# V7_2024-09-14.net
KiCad netlist of a schematic drawn in EasyEDA Pro
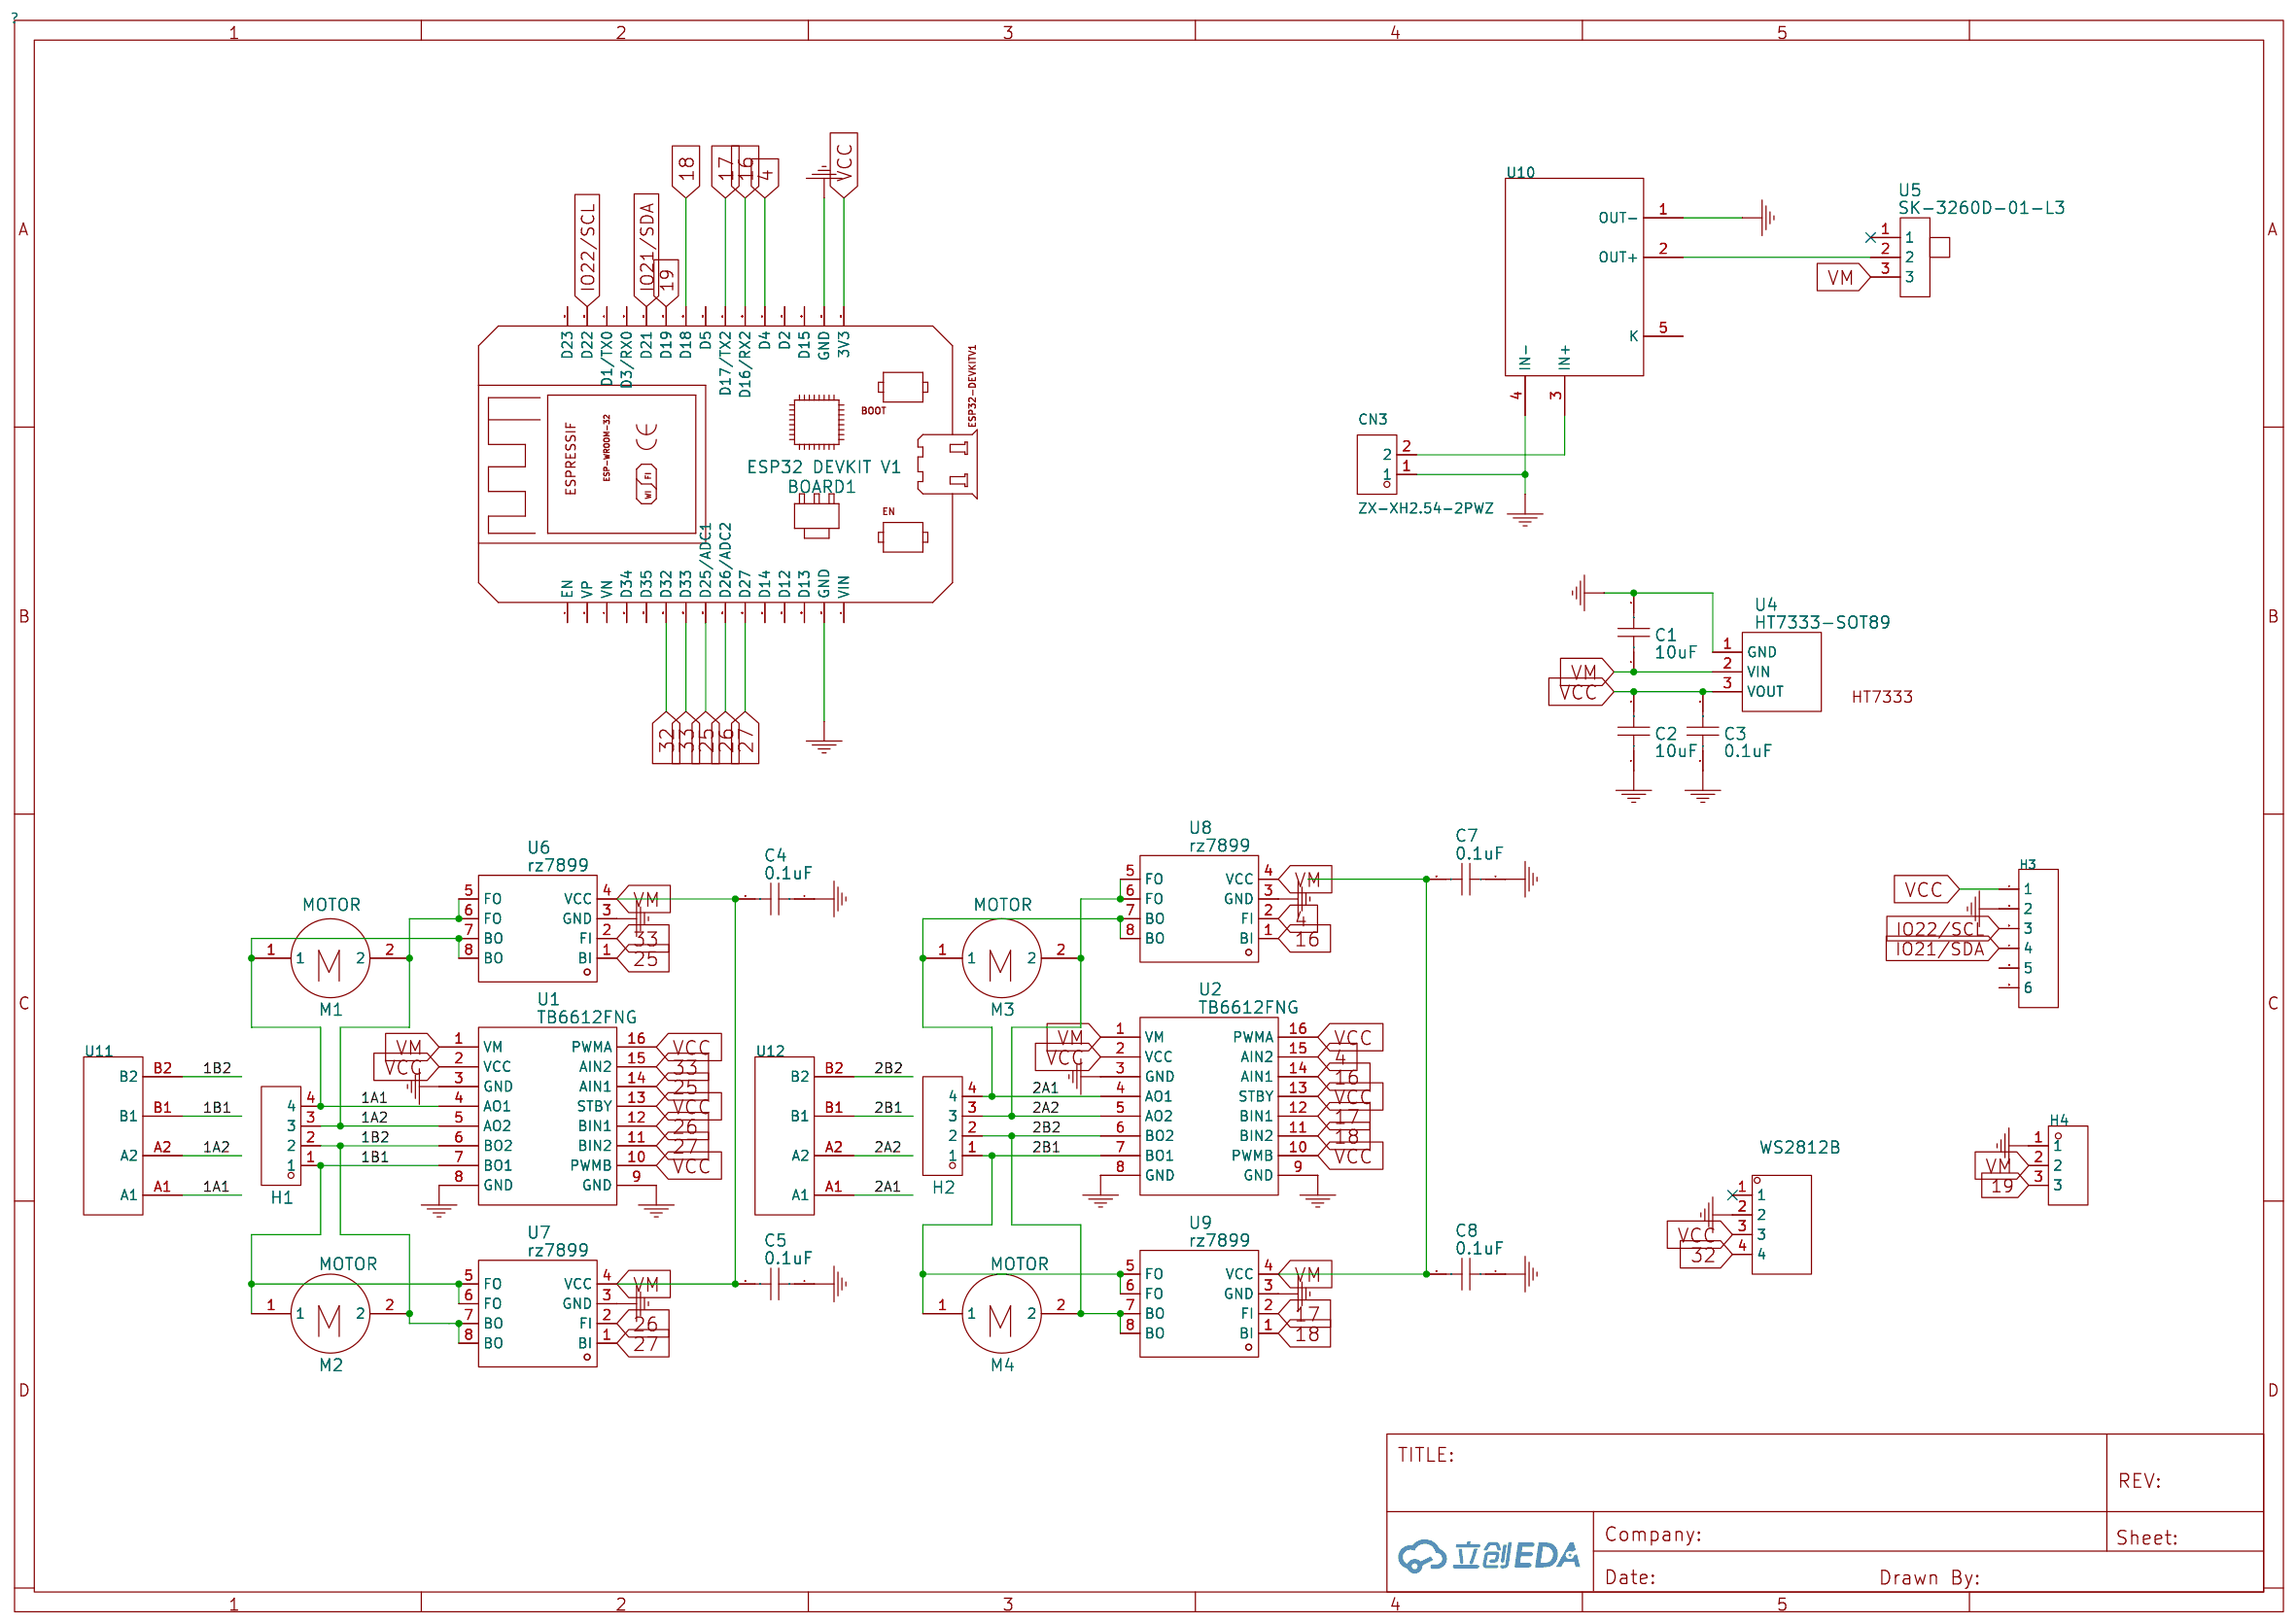
[diagram p0: schematic sheet]

(export (version "E")
  (design (tool "Eeschema 10.0.6"))
  (components
    (comp (ref "BOARD1")
      (value "ESP32 DEVKIT V1")
      (footprint "easyedapro:ESP32-DEVKITV1")
      (libsource (lib "easyedapro") (part "ESP32 DEVKIT V1"))
    )
    (comp (ref "C1")
      (value "10uF")
      (footprint "easyedapro:C0805")
      (fields
        (field (name "Manufacturer Part") "0603F225M250NT")
        (field (name "Manufacturer") "Guangdong Fenghua Advanced Tech")
      )
      (libsource (lib "easyedapro") (part "10uF"))
    )
    (comp (ref "C2")
      (value "10uF")
      (footprint "easyedapro:C0805")
      (fields
        (field (name "Manufacturer Part") "0603F225M250NT")
        (field (name "Manufacturer") "Guangdong Fenghua Advanced Tech")
      )
      (libsource (lib "easyedapro") (part "10uF"))
    )
    (comp (ref "C3")
      (value "0.1uF")
      (footprint "easyedapro:C0805")
      (fields
        (field (name "Manufacturer Part") "0603F225M250NT")
        (field (name "Manufacturer") "Guangdong Fenghua Advanced Tech")
      )
      (libsource (lib "easyedapro") (part "10uF"))
    )
    (comp (ref "C4")
      (value "0.1uF")
      (footprint "easyedapro:C0805")
      (fields
        (field (name "Manufacturer Part") "0603F225M250NT")
        (field (name "Manufacturer") "Guangdong Fenghua Advanced Tech")
      )
      (libsource (lib "easyedapro") (part "10uF"))
    )
    (comp (ref "C5")
      (value "0.1uF")
      (footprint "easyedapro:C0805")
      (fields
        (field (name "Manufacturer Part") "0603F225M250NT")
        (field (name "Manufacturer") "Guangdong Fenghua Advanced Tech")
      )
      (libsource (lib "easyedapro") (part "10uF"))
    )
    (comp (ref "C7")
      (value "0.1uF")
      (footprint "easyedapro:C0805")
      (fields
        (field (name "Manufacturer Part") "0603F225M250NT")
        (field (name "Manufacturer") "Guangdong Fenghua Advanced Tech")
      )
      (libsource (lib "easyedapro") (part "10uF"))
    )
    (comp (ref "C8")
      (value "0.1uF")
      (footprint "easyedapro:C0805")
      (fields
        (field (name "Manufacturer Part") "0603F225M250NT")
        (field (name "Manufacturer") "Guangdong Fenghua Advanced Tech")
      )
      (libsource (lib "easyedapro") (part "10uF"))
    )
    (comp (ref "CN3")
      (value "ZX-XH2.54-2PWZ")
      (footprint "easyedapro:CONN-TH_2P-P2.50_ZX-XH2.54-2PWZ")
      (fields (field (name "Manufacturer") "Megastar(兆星)"))
      (libsource (lib "easyedapro") (part "ZX-XH2.54-2PWZ"))
    )
    (comp (ref "H1")
      (value "GP25-2521WV-4P")
      (footprint "easyedapro:HDR-TH_4P-P2.54-V-F")
      (fields (field (name "Manufacturer") "GEPU(歌普)"))
      (libsource (lib "easyedapro") (part "GP25-2521WV-4P"))
    )
    (comp (ref "H2")
      (value "GP25-2521WV-4P")
      (footprint "easyedapro:HDR-TH_4P-P2.54-V-F")
      (fields (field (name "Manufacturer") "GEPU(歌普)"))
      (libsource (lib "easyedapro") (part "GP25-2521WV-4P"))
    )
    (comp (ref "H3")
      (value "~")
      (footprint "easyedapro:HDR-TH_6P-P2.54-V-M-1")
      (libsource (lib "easyedapro") (part "Header-Male-2.54_1x6"))
    )
    (comp (ref "H4")
      (value "~")
      (footprint "easyedapro:HDR-TH_3P-P2.54-V-M")
      (libsource (lib "easyedapro") (part "PZ254V-11-03P_C2937625"))
    )
    (comp (ref "M1")
      (value "MOTOR")
      (footprint "easyedapro:MOTOR")
      (libsource (lib "easyedapro") (part "MOTOR"))
    )
    (comp (ref "M2")
      (value "MOTOR")
      (footprint "easyedapro:MOTOR")
      (libsource (lib "easyedapro") (part "MOTOR"))
    )
    (comp (ref "M3")
      (value "MOTOR")
      (footprint "easyedapro:MOTOR")
      (libsource (lib "easyedapro") (part "MOTOR"))
    )
    (comp (ref "M4")
      (value "MOTOR")
      (footprint "easyedapro:MOTOR")
      (libsource (lib "easyedapro") (part "MOTOR"))
    )
    (comp (ref "U1")
      (value "TB6612FNG")
      (footprint "easyedapro:TB6612FNG")
      (libsource (lib "easyedapro") (part "TB6612FNG"))
    )
    (comp (ref "U2")
      (value "TB6612FNG")
      (footprint "easyedapro:TB6612FNG")
      (libsource (lib "easyedapro") (part "TB6612FNG"))
    )
    (comp (ref "U4")
      (value "HT7333-SOT89")
      (footprint "easyedapro:HT7333_SOT-89")
      (libsource (lib "easyedapro") (part "HT7333-SOT89"))
    )
    (comp (ref "U5")
      (value "SK-3260D-01-L3")
      (footprint "easyedapro:SW-TH_SK-3260D-01-LX")
      (fields (field (name "Manufacturer") "XKB Connectivity"))
      (libsource (lib "easyedapro") (part "SK-3260D-01-L3"))
    )
    (comp (ref "U6")
      (value "rz7899")
      (footprint "easyedapro:SOP-8_L4.9-W3.9-P1.27-LS6.0-BL")
      (fields (field (name "Manufacturer") "RZ"))
      (libsource (lib "easyedapro") (part "rz7899"))
    )
    (comp (ref "U7")
      (value "rz7899")
      (footprint "easyedapro:SOP-8_L4.9-W3.9-P1.27-LS6.0-BL")
      (fields (field (name "Manufacturer") "RZ"))
      (libsource (lib "easyedapro") (part "rz7899"))
    )
    (comp (ref "U8")
      (value "rz7899")
      (footprint "easyedapro:SOP-8_L4.9-W3.9-P1.27-LS6.0-BL")
      (fields (field (name "Manufacturer") "RZ"))
      (libsource (lib "easyedapro") (part "rz7899"))
    )
    (comp (ref "U9")
      (value "rz7899")
      (footprint "easyedapro:SOP-8_L4.9-W3.9-P1.27-LS6.0-BL")
      (fields (field (name "Manufacturer") "RZ"))
      (libsource (lib "easyedapro") (part "rz7899"))
    )
    (comp (ref "U10") (value "~") (footprint "easyedapro:5V模块") (libsource (lib "easyedapro") (part "5V模块")))
    (comp (ref "U11") (value "~") (libsource (lib "easyedapro") (part "M")))
    (comp (ref "U12") (value "~") (libsource (lib "easyedapro") (part "M")))
    (comp (ref "WS2812B")
      (value "MTP125-1104S1")
      (footprint "easyedapro:HDR-TH_4P-P2.54-V")
      (fields (field (name "Manufacturer") "MINTRON"))
      (libsource (lib "easyedapro") (part "MTP125-1104S1"))
    )
  )
  (nets
    (net (code "1") (name "/1A1") (class "Default")
      (node (ref "H1") (pin "4") (pinfunction "4_4") (pintype "input"))
      (node (ref "M1") (pin "1") (pinfunction "1_1") (pintype "input"))
      (node (ref "U1") (pin "4") (pinfunction "AO1_4") (pintype "input"))
      (node (ref "U11") (pin "A1") (pinfunction "A1_A1") (pintype "input"))
      (node (ref "U6") (pin "7") (pinfunction "BO_7") (pintype "input"))
      (node (ref "U6") (pin "8") (pinfunction "BO_8") (pintype "input"))
    )
    (net (code "2") (name "/1A2") (class "Default")
      (node (ref "H1") (pin "3") (pinfunction "3_3") (pintype "input"))
      (node (ref "M1") (pin "2") (pinfunction "2_2") (pintype "input"))
      (node (ref "U1") (pin "5") (pinfunction "AO2_5") (pintype "input"))
      (node (ref "U11") (pin "A2") (pinfunction "A2_A2") (pintype "input"))
      (node (ref "U6") (pin "5") (pinfunction "FO_5") (pintype "input"))
      (node (ref "U6") (pin "6") (pinfunction "FO_6") (pintype "input"))
    )
    (net (code "3") (name "/1B1") (class "Default")
      (node (ref "H1") (pin "1") (pinfunction "1_1") (pintype "input"))
      (node (ref "M2") (pin "1") (pinfunction "1_1") (pintype "input"))
      (node (ref "U1") (pin "7") (pinfunction "BO1_7") (pintype "input"))
      (node (ref "U11") (pin "B1") (pinfunction "B1_B1") (pintype "input"))
      (node (ref "U7") (pin "5") (pinfunction "FO_5") (pintype "input"))
      (node (ref "U7") (pin "6") (pinfunction "FO_6") (pintype "input"))
    )
    (net (code "4") (name "/1B2") (class "Default")
      (node (ref "H1") (pin "2") (pinfunction "2_2") (pintype "input"))
      (node (ref "M2") (pin "2") (pinfunction "2_2") (pintype "input"))
      (node (ref "U1") (pin "6") (pinfunction "BO2_6") (pintype "input"))
      (node (ref "U11") (pin "B2") (pinfunction "B2_B2") (pintype "input"))
      (node (ref "U7") (pin "7") (pinfunction "BO_7") (pintype "input"))
      (node (ref "U7") (pin "8") (pinfunction "BO_8") (pintype "input"))
    )
    (net (code "5") (name "/2A1") (class "Default")
      (node (ref "H2") (pin "4") (pinfunction "4_4") (pintype "input"))
      (node (ref "M3") (pin "1") (pinfunction "1_1") (pintype "input"))
      (node (ref "U12") (pin "A1") (pinfunction "A1_A1") (pintype "input"))
      (node (ref "U2") (pin "4") (pinfunction "AO1_4") (pintype "input"))
      (node (ref "U8") (pin "7") (pinfunction "BO_7") (pintype "input"))
      (node (ref "U8") (pin "8") (pinfunction "BO_8") (pintype "input"))
    )
    (net (code "6") (name "/2A2") (class "Default")
      (node (ref "H2") (pin "3") (pinfunction "3_3") (pintype "input"))
      (node (ref "M3") (pin "2") (pinfunction "2_2") (pintype "input"))
      (node (ref "U12") (pin "A2") (pinfunction "A2_A2") (pintype "input"))
      (node (ref "U2") (pin "5") (pinfunction "AO2_5") (pintype "input"))
      (node (ref "U8") (pin "5") (pinfunction "FO_5") (pintype "input"))
      (node (ref "U8") (pin "6") (pinfunction "FO_6") (pintype "input"))
    )
    (net (code "7") (name "/2B1") (class "Default")
      (node (ref "H2") (pin "1") (pinfunction "1_1") (pintype "input"))
      (node (ref "M4") (pin "1") (pinfunction "1_1") (pintype "input"))
      (node (ref "U12") (pin "B1") (pinfunction "B1_B1") (pintype "input"))
      (node (ref "U2") (pin "7") (pinfunction "BO1_7") (pintype "input"))
      (node (ref "U9") (pin "5") (pinfunction "FO_5") (pintype "input"))
      (node (ref "U9") (pin "6") (pinfunction "FO_6") (pintype "input"))
    )
    (net (code "8") (name "/2B2") (class "Default")
      (node (ref "H2") (pin "2") (pinfunction "2_2") (pintype "input"))
      (node (ref "M4") (pin "2") (pinfunction "2_2") (pintype "input"))
      (node (ref "U12") (pin "B2") (pinfunction "B2_B2") (pintype "input"))
      (node (ref "U2") (pin "6") (pinfunction "BO2_6") (pintype "input"))
      (node (ref "U9") (pin "7") (pinfunction "BO_7") (pintype "input"))
      (node (ref "U9") (pin "8") (pinfunction "BO_8") (pintype "input"))
    )
    (net (code "9") (name "4") (class "Default")
      (node (ref "BOARD1") (pin "D4") (pinfunction "D4_D4") (pintype "bidirectional"))
      (node (ref "U2") (pin "15") (pinfunction "AIN2_15") (pintype "input"))
      (node (ref "U8") (pin "2") (pinfunction "FI_2") (pintype "input"))
    )
    (net (code "10") (name "16") (class "Default")
      (node (ref "BOARD1") (pin "D16") (pinfunction "D16/RX2_D16") (pintype "bidirectional"))
      (node (ref "U2") (pin "14") (pinfunction "AIN1_14") (pintype "input"))
      (node (ref "U8") (pin "1") (pinfunction "BI_1") (pintype "input"))
    )
    (net (code "11") (name "17") (class "Default")
      (node (ref "BOARD1") (pin "D17") (pinfunction "D17/TX2_D17") (pintype "bidirectional"))
      (node (ref "U2") (pin "12") (pinfunction "BIN1_12") (pintype "input"))
      (node (ref "U9") (pin "2") (pinfunction "FI_2") (pintype "input"))
    )
    (net (code "12") (name "18") (class "Default")
      (node (ref "BOARD1") (pin "D18") (pinfunction "D18_D18") (pintype "bidirectional"))
      (node (ref "U2") (pin "11") (pinfunction "BIN2_11") (pintype "input"))
      (node (ref "U9") (pin "1") (pinfunction "BI_1") (pintype "input"))
    )
    (net (code "13") (name "19") (class "Default")
      (node (ref "BOARD1") (pin "D19") (pinfunction "D19_D19") (pintype "bidirectional"))
      (node (ref "H4") (pin "3") (pinfunction "3_3") (pintype "input"))
    )
    (net (code "14") (name "25") (class "Default")
      (node (ref "BOARD1") (pin "D25") (pinfunction "D25/ADC1_D25") (pintype "bidirectional"))
      (node (ref "U1") (pin "14") (pinfunction "AIN1_14") (pintype "input"))
      (node (ref "U6") (pin "1") (pinfunction "BI_1") (pintype "input"))
    )
    (net (code "15") (name "26") (class "Default")
      (node (ref "BOARD1") (pin "D26") (pinfunction "D26/ADC2_D26") (pintype "bidirectional"))
      (node (ref "U1") (pin "12") (pinfunction "BIN1_12") (pintype "input"))
      (node (ref "U7") (pin "2") (pinfunction "FI_2") (pintype "input"))
    )
    (net (code "16") (name "27") (class "Default")
      (node (ref "BOARD1") (pin "D27") (pinfunction "D27_D27") (pintype "bidirectional"))
      (node (ref "U1") (pin "11") (pinfunction "BIN2_11") (pintype "input"))
      (node (ref "U7") (pin "1") (pinfunction "BI_1") (pintype "input"))
    )
    (net (code "17") (name "32") (class "Default")
      (node (ref "BOARD1") (pin "D32") (pinfunction "D32_D32") (pintype "bidirectional"))
      (node (ref "WS2812B") (pin "4") (pinfunction "4_4") (pintype "input"))
    )
    (net (code "18") (name "33") (class "Default")
      (node (ref "BOARD1") (pin "D33") (pinfunction "D33_D33") (pintype "bidirectional"))
      (node (ref "U1") (pin "15") (pinfunction "AIN2_15") (pintype "input"))
      (node (ref "U6") (pin "2") (pinfunction "FI_2") (pintype "input"))
    )
    (net (code "19") (name "GND") (class "Default")
      (node (ref "BOARD1") (pin "GND") (pinfunction "GND_GND") (pintype "bidirectional"))
      (node (ref "BOARD1") (pin "GND@1") (pinfunction "GND_GND@1") (pintype "bidirectional"))
      (node (ref "C1") (pin "2") (pinfunction "2_2") (pintype "input"))
      (node (ref "C2") (pin "1") (pinfunction "1_1") (pintype "input"))
      (node (ref "C3") (pin "1") (pinfunction "1_1") (pintype "input"))
      (node (ref "C4") (pin "1") (pinfunction "1_1") (pintype "input"))
      (node (ref "C5") (pin "1") (pinfunction "1_1") (pintype "input"))
      (node (ref "C7") (pin "1") (pinfunction "1_1") (pintype "input"))
      (node (ref "C8") (pin "1") (pinfunction "1_1") (pintype "input"))
      (node (ref "CN3") (pin "1") (pinfunction "1_1") (pintype "unspecified"))
      (node (ref "H3") (pin "2") (pinfunction "2_2") (pintype "input"))
      (node (ref "H4") (pin "1") (pinfunction "1_1") (pintype "input"))
      (node (ref "U1") (pin "3") (pinfunction "GND_3") (pintype "input"))
      (node (ref "U1") (pin "8") (pinfunction "GND_8") (pintype "input"))
      (node (ref "U1") (pin "9") (pinfunction "GND_9") (pintype "input"))
      (node (ref "U10") (pin "1") (pinfunction "OUT-_1") (pintype "input"))
      (node (ref "U10") (pin "4") (pinfunction "IN-_4") (pintype "input"))
      (node (ref "U2") (pin "3") (pinfunction "GND_3") (pintype "input"))
      (node (ref "U2") (pin "8") (pinfunction "GND_8") (pintype "input"))
      (node (ref "U2") (pin "9") (pinfunction "GND_9") (pintype "input"))
      (node (ref "U4") (pin "1") (pinfunction "GND_1") (pintype "input"))
      (node (ref "U6") (pin "3") (pinfunction "GND_3") (pintype "input"))
      (node (ref "U7") (pin "3") (pinfunction "GND_3") (pintype "input"))
      (node (ref "U8") (pin "3") (pinfunction "GND_3") (pintype "input"))
      (node (ref "U9") (pin "3") (pinfunction "GND_3") (pintype "input"))
      (node (ref "WS2812B") (pin "2") (pinfunction "2_2") (pintype "input"))
    )
    (net (code "20") (name "IO21{slash}SDA") (class "Default")
      (node (ref "BOARD1") (pin "D21") (pinfunction "D21_D21") (pintype "bidirectional"))
      (node (ref "H3") (pin "4") (pinfunction "4_4") (pintype "input"))
    )
    (net (code "21") (name "IO22{slash}SCL") (class "Default")
      (node (ref "BOARD1") (pin "D22") (pinfunction "D22_D22") (pintype "bidirectional"))
      (node (ref "H3") (pin "3") (pinfunction "3_3") (pintype "input"))
    )
    (net (code "22") (name "Net-(U10-IN+)") (class "Default")
      (node (ref "CN3") (pin "2") (pinfunction "2_2") (pintype "unspecified"))
      (node (ref "U10") (pin "3") (pinfunction "IN+_3") (pintype "input"))
    )
    (net (code "23") (name "Net-(U10-OUT+)") (class "Default")
      (node (ref "U10") (pin "2") (pinfunction "OUT+_2") (pintype "input"))
      (node (ref "U5") (pin "2") (pinfunction "2_2") (pintype "input"))
    )
    (net (code "24") (name "VCC") (class "Default")
      (node (ref "BOARD1") (pin "3V3") (pinfunction "3V3_3V3") (pintype "bidirectional"))
      (node (ref "C2") (pin "2") (pinfunction "2_2") (pintype "input"))
      (node (ref "C3") (pin "2") (pinfunction "2_2") (pintype "input"))
      (node (ref "H3") (pin "1") (pinfunction "1_1") (pintype "input"))
      (node (ref "U1") (pin "10") (pinfunction "PWMB_10") (pintype "input"))
      (node (ref "U1") (pin "13") (pinfunction "STBY_13") (pintype "input"))
      (node (ref "U1") (pin "16") (pinfunction "PWMA_16") (pintype "input"))
      (node (ref "U1") (pin "2") (pinfunction "VCC_2") (pintype "input"))
      (node (ref "U2") (pin "10") (pinfunction "PWMB_10") (pintype "input"))
      (node (ref "U2") (pin "13") (pinfunction "STBY_13") (pintype "input"))
      (node (ref "U2") (pin "16") (pinfunction "PWMA_16") (pintype "input"))
      (node (ref "U2") (pin "2") (pinfunction "VCC_2") (pintype "input"))
      (node (ref "U4") (pin "3") (pinfunction "VOUT_3") (pintype "input"))
      (node (ref "WS2812B") (pin "3") (pinfunction "3_3") (pintype "input"))
    )
    (net (code "25") (name "VM") (class "Default")
      (node (ref "C1") (pin "1") (pinfunction "1_1") (pintype "input"))
      (node (ref "C4") (pin "2") (pinfunction "2_2") (pintype "input"))
      (node (ref "C5") (pin "2") (pinfunction "2_2") (pintype "input"))
      (node (ref "C7") (pin "2") (pinfunction "2_2") (pintype "input"))
      (node (ref "C8") (pin "2") (pinfunction "2_2") (pintype "input"))
      (node (ref "H4") (pin "2") (pinfunction "2_2") (pintype "input"))
      (node (ref "U1") (pin "1") (pinfunction "VM_1") (pintype "input"))
      (node (ref "U2") (pin "1") (pinfunction "VM_1") (pintype "input"))
      (node (ref "U4") (pin "2") (pinfunction "VIN_2") (pintype "input"))
      (node (ref "U5") (pin "3") (pinfunction "3_3") (pintype "input"))
      (node (ref "U6") (pin "4") (pinfunction "VCC_4") (pintype "input"))
      (node (ref "U7") (pin "4") (pinfunction "VCC_4") (pintype "input"))
      (node (ref "U8") (pin "4") (pinfunction "VCC_4") (pintype "input"))
      (node (ref "U9") (pin "4") (pinfunction "VCC_4") (pintype "input"))
    )
    (net (code "26") (name "unconnected-(BOARD1-D1{slash}TX0-PadD1)") (class "Default")
      (node (ref "BOARD1") (pin "D1") (pinfunction "D1/TX0_D1") (pintype "bidirectional"))
    )
    (net (code "27") (name "unconnected-(BOARD1-D3{slash}RX0-PadD3)") (class "Default")
      (node (ref "BOARD1") (pin "D3") (pinfunction "D3/RX0_D3") (pintype "bidirectional"))
    )
    (net (code "28") (name "unconnected-(BOARD1-PadD2)") (class "Default")
      (node (ref "BOARD1") (pin "D2") (pinfunction "D2_D2") (pintype "bidirectional"))
    )
    (net (code "29") (name "unconnected-(BOARD1-PadD5)") (class "Default")
      (node (ref "BOARD1") (pin "D5") (pinfunction "D5_D5") (pintype "bidirectional"))
    )
    (net (code "30") (name "unconnected-(BOARD1-PadD12)") (class "Default")
      (node (ref "BOARD1") (pin "D12") (pinfunction "D12_D12") (pintype "bidirectional"))
    )
    (net (code "31") (name "unconnected-(BOARD1-PadD13)") (class "Default")
      (node (ref "BOARD1") (pin "D13") (pinfunction "D13_D13") (pintype "bidirectional"))
    )
    (net (code "32") (name "unconnected-(BOARD1-PadD14)") (class "Default")
      (node (ref "BOARD1") (pin "D14") (pinfunction "D14_D14") (pintype "bidirectional"))
    )
    (net (code "33") (name "unconnected-(BOARD1-PadD15)") (class "Default")
      (node (ref "BOARD1") (pin "D15") (pinfunction "D15_D15") (pintype "bidirectional"))
    )
    (net (code "34") (name "unconnected-(BOARD1-PadD23)") (class "Default")
      (node (ref "BOARD1") (pin "D23") (pinfunction "D23_D23") (pintype "bidirectional"))
    )
    (net (code "35") (name "unconnected-(BOARD1-PadD34)") (class "Default")
      (node (ref "BOARD1") (pin "D34") (pinfunction "D34_D34") (pintype "bidirectional"))
    )
    (net (code "36") (name "unconnected-(BOARD1-PadD35)") (class "Default")
      (node (ref "BOARD1") (pin "D35") (pinfunction "D35_D35") (pintype "bidirectional"))
    )
    (net (code "37") (name "unconnected-(BOARD1-PadEN)") (class "Default")
      (node (ref "BOARD1") (pin "EN") (pinfunction "EN_EN") (pintype "bidirectional"))
    )
    (net (code "38") (name "unconnected-(BOARD1-PadVIN)") (class "Default")
      (node (ref "BOARD1") (pin "VIN") (pinfunction "VIN_VIN") (pintype "bidirectional"))
    )
    (net (code "39") (name "unconnected-(BOARD1-PadVN)") (class "Default")
      (node (ref "BOARD1") (pin "VN") (pinfunction "VN_VN") (pintype "bidirectional"))
    )
    (net (code "40") (name "unconnected-(BOARD1-PadVP)") (class "Default")
      (node (ref "BOARD1") (pin "VP") (pinfunction "VP_VP") (pintype "bidirectional"))
    )
    (net (code "41") (name "unconnected-(H3-Pad5)") (class "Default")
      (node (ref "H3") (pin "5") (pinfunction "5_5") (pintype "input"))
    )
    (net (code "42") (name "unconnected-(H3-Pad6)") (class "Default")
      (node (ref "H3") (pin "6") (pinfunction "6_6") (pintype "input"))
    )
    (net (code "43") (name "unconnected-(U5-Pad1)") (class "Default")
      (node (ref "U5") (pin "1") (pinfunction "1_1") (pintype "input+no_connect"))
    )
    (net (code "44") (name "unconnected-(U10-K-Pad5)") (class "Default")
      (node (ref "U10") (pin "5") (pinfunction "K_5") (pintype "input"))
    )
    (net (code "45") (name "unconnected-(WS2812B-Pad1)") (class "Default")
      (node (ref "WS2812B") (pin "1") (pinfunction "1_1") (pintype "input+no_connect"))
    )
  )
)
